# Power_Supplies.net
KiCad netlist of a schematic drawn in Altium Designer
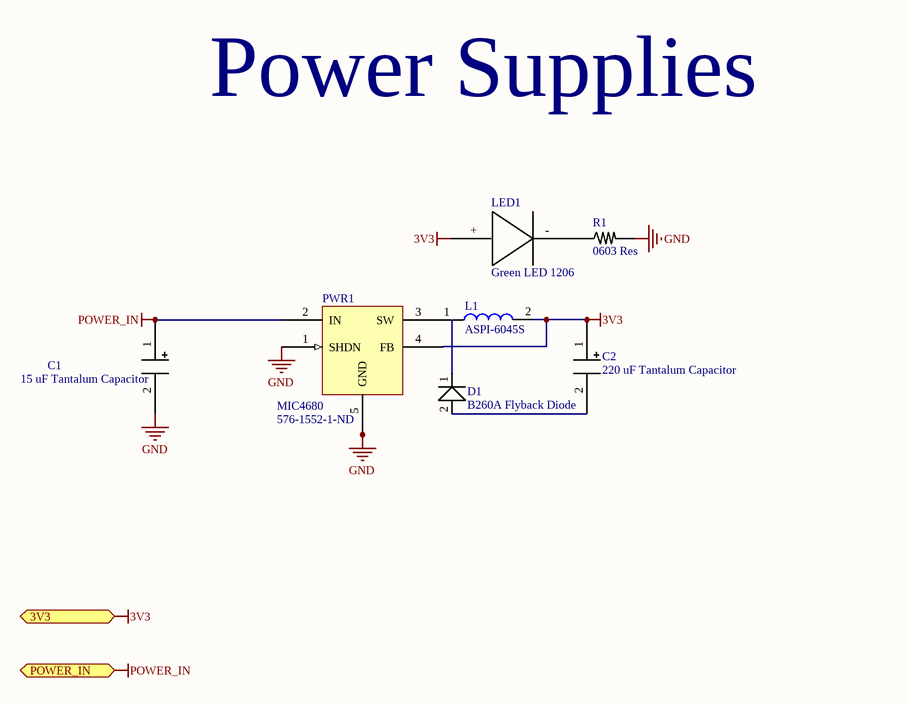
[diagram p0: Power_Supplies.SchDoc]

(export (version "E")
  (design (tool "Eeschema 10.0.6"))
  (components
    (comp (ref "C1")
      (value "15 uF Tantalum Capacitor")
      (footprint "1206 (POLAR)")
      (description "1206 Surface Mount Capacitor")
      (libsource (lib "CUBAJA") (part "15 uF Tantalum Capacitor"))
    )
    (comp (ref "C2")
      (value "220 uF Tantalum Capacitor")
      (footprint "1206 (POLAR)")
      (description "1206 Surface Mount Capacitor")
      (libsource (lib "CUBAJA") (part "15 uF Tantalum Capacitor"))
    )
    (comp (ref "D1")
      (value "B260A Flyback Diode")
      (footprint "DO-214AC")
      (libsource (lib "CUBAJA") (part "B260A Flyback Diode"))
    )
    (comp (ref "L1")
      (value "ASPI-6045S")
      (footprint "ASPI-6045")
      (description "68 uH 1.2A surface mount inductor")
      (libsource (lib "CUBAJA") (part "ASPI-6045S"))
    )
    (comp (ref "LED1")
      (value "Green LED 1206")
      (footprint "Cathode Mark 1206 led footprint")
      (description "Green surface mount LED")
      (libsource (lib "CUBAJA") (part "1206 Green LED"))
    )
    (comp (ref "PWR1")
      (value "MIC4680")
      (footprint "TJA1040")
      (description "3.3V Fixed Switching Regulator 1A")
      (fields (field (name "SUPPLIER PART NUMBER 1") "576-1552-1-ND"))
      (libsource (lib "CornellBajaLibrary") (part "MIC4680"))
    )
    (comp (ref "R1")
      (value "0603 Res")
      (footprint "0603/1608 SMD Resistor")
      (libsource (lib "CornellBajaLibrary") (part "0603 Res"))
    )
  )
  (nets
    (net (code "1") (name "3V3") (class "Default")
      (node (ref "C2") (pin "1") (pinfunction "1_1") (pintype "passive"))
      (node (ref "L1") (pin "2") (pinfunction "2_2") (pintype "passive"))
      (node (ref "LED1") (pin "+") (pintype "passive"))
      (node (ref "PWR1") (pin "4") (pinfunction "FB_4") (pintype "passive"))
    )
    (net (code "2") (name "GND") (class "Default")
      (node (ref "C1") (pin "2") (pinfunction "2_2") (pintype "passive"))
      (node (ref "PWR1") (pin "1") (pinfunction "SHDN_1") (pintype "input"))
      (node (ref "PWR1") (pin "5") (pinfunction "GND_5") (pintype "passive"))
      (node (ref "PWR1") (pin "6") (pinfunction "6_6") (pintype "passive"))
      (node (ref "PWR1") (pin "7") (pinfunction "7_7") (pintype "passive"))
      (node (ref "PWR1") (pin "8") (pinfunction "8_8") (pintype "passive"))
      (node (ref "R1") (pin "2") (pinfunction "2_2") (pintype "passive"))
    )
    (net (code "3") (name "Net-(C2-Pad2)") (class "Default")
      (node (ref "C2") (pin "2") (pinfunction "2_2") (pintype "passive"))
      (node (ref "D1") (pin "2") (pintype "passive"))
    )
    (net (code "4") (name "Net-(LED1-Pad-)") (class "Default")
      (node (ref "LED1") (pin "-") (pintype "passive"))
      (node (ref "R1") (pin "1") (pinfunction "1_1") (pintype "passive"))
    )
    (net (code "5") (name "Net-(PWR1-SW)") (class "Default")
      (node (ref "L1") (pin "1") (pinfunction "1_1") (pintype "passive"))
      (node (ref "PWR1") (pin "3") (pinfunction "SW_3") (pintype "passive"))
    )
    (net (code "6") (name "POWER_IN") (class "Default")
      (node (ref "C1") (pin "1") (pinfunction "1_1") (pintype "passive"))
      (node (ref "PWR1") (pin "2") (pinfunction "IN_2") (pintype "passive"))
    )
    (net (code "7") (name "unconnected-(D1-Pad1)") (class "Default")
      (node (ref "D1") (pin "1") (pintype "passive"))
    )
  )
)
